# AVR_Board_4_0_Ports_-Old.net
KiCad netlist of a schematic drawn in Altium Designer
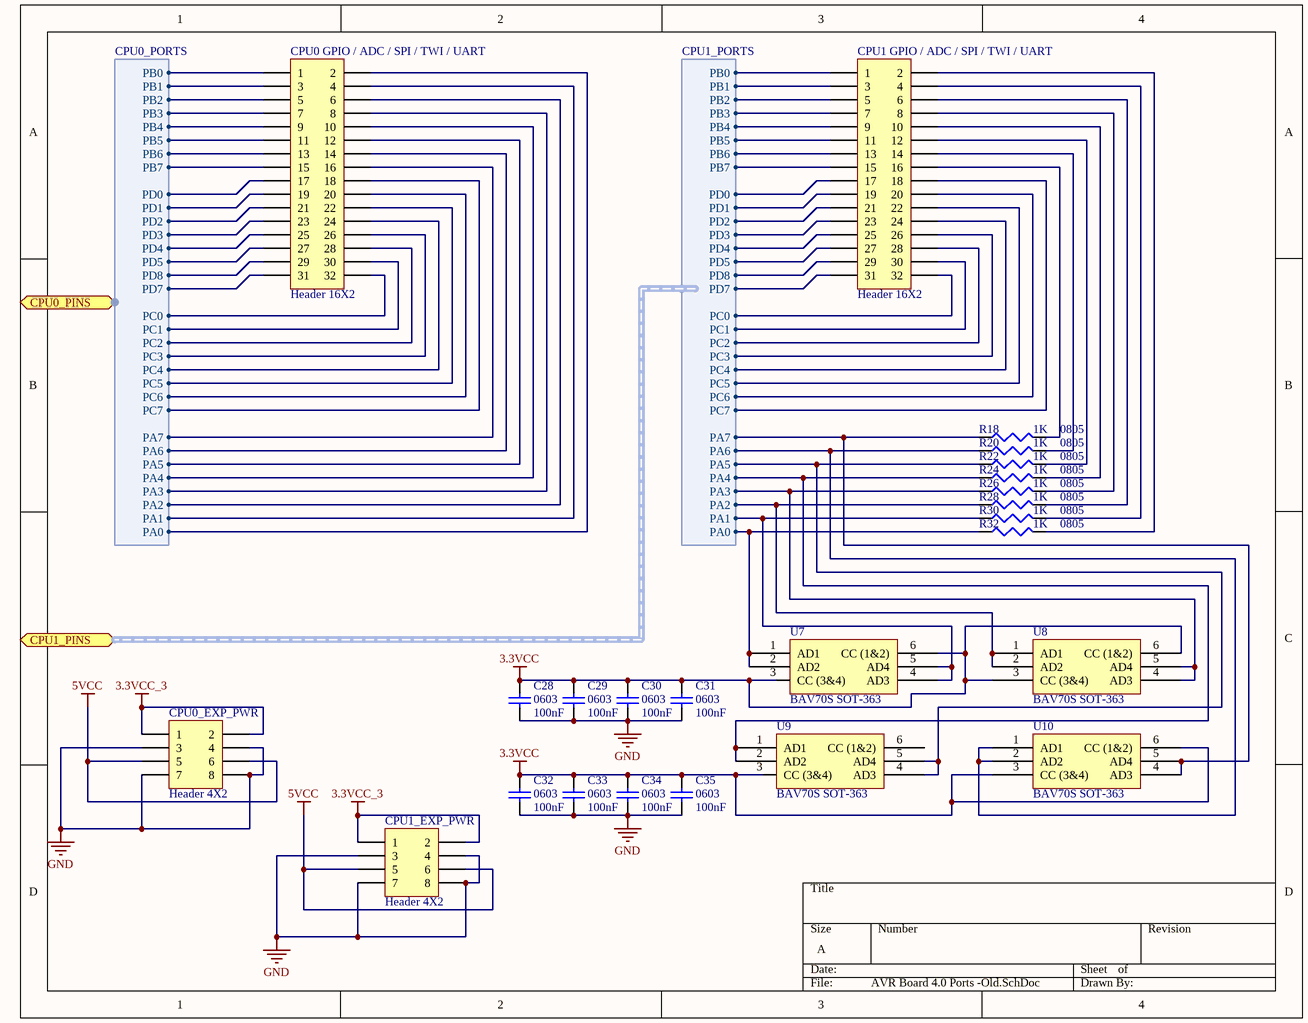
[diagram p0: AVR Board 4.0 Ports -Old.SchDoc]

(export (version "E")
  (design (tool "Eeschema 10.0.6"))
  (components
    (comp (ref "C28")
      (value "0603")
      (footprint "C1206")
      (description "Capacitor (Semiconductor SIM Model)")
      (fields (field (name "ALTIUM_VALUE") "100nF") (field (name "PUBLISHER") "Altium Limited"))
      (libsource (lib "Miscellaneous Devices") (part "Cap Semi"))
    )
    (comp (ref "C29")
      (value "0603")
      (footprint "C1206")
      (description "Capacitor (Semiconductor SIM Model)")
      (fields (field (name "ALTIUM_VALUE") "100nF") (field (name "PUBLISHER") "Altium Limited"))
      (libsource (lib "Miscellaneous Devices") (part "Cap Semi"))
    )
    (comp (ref "C30")
      (value "0603")
      (footprint "C1206")
      (description "Capacitor (Semiconductor SIM Model)")
      (fields (field (name "ALTIUM_VALUE") "100nF") (field (name "PUBLISHER") "Altium Limited"))
      (libsource (lib "Miscellaneous Devices") (part "Cap Semi"))
    )
    (comp (ref "C31")
      (value "0603")
      (footprint "C1206")
      (description "Capacitor (Semiconductor SIM Model)")
      (fields (field (name "ALTIUM_VALUE") "100nF") (field (name "PUBLISHER") "Altium Limited"))
      (libsource (lib "Miscellaneous Devices") (part "Cap Semi"))
    )
    (comp (ref "C32")
      (value "0603")
      (footprint "C1206")
      (description "Capacitor (Semiconductor SIM Model)")
      (fields (field (name "ALTIUM_VALUE") "100nF") (field (name "PUBLISHER") "Altium Limited"))
      (libsource (lib "Miscellaneous Devices") (part "Cap Semi"))
    )
    (comp (ref "C33")
      (value "0603")
      (footprint "C1206")
      (description "Capacitor (Semiconductor SIM Model)")
      (fields (field (name "ALTIUM_VALUE") "100nF") (field (name "PUBLISHER") "Altium Limited"))
      (libsource (lib "Miscellaneous Devices") (part "Cap Semi"))
    )
    (comp (ref "C34")
      (value "0603")
      (footprint "C1206")
      (description "Capacitor (Semiconductor SIM Model)")
      (fields (field (name "ALTIUM_VALUE") "100nF") (field (name "PUBLISHER") "Altium Limited"))
      (libsource (lib "Miscellaneous Devices") (part "Cap Semi"))
    )
    (comp (ref "C35")
      (value "0603")
      (footprint "C1206")
      (description "Capacitor (Semiconductor SIM Model)")
      (fields (field (name "ALTIUM_VALUE") "100nF") (field (name "PUBLISHER") "Altium Limited"))
      (libsource (lib "Miscellaneous Devices") (part "Cap Semi"))
    )
    (comp (ref "CPU0 GPIO / ADC / SPI / TWI / UART")
      (value "Header 16X2")
      (footprint "HDR2X16")
      (description "Header, 16-Pin, Dual row")
      (fields (field (name "PUBLISHER") "Altium Limited"))
      (libsource (lib "Miscellaneous Connectors") (part "Header 16X2"))
    )
    (comp (ref "CPU0_EXP_PWR")
      (value "Header 4X2")
      (footprint "HDR2X4")
      (description "Header, 4-Pin, Dual row")
      (fields (field (name "PUBLISHER") "Altium Limited"))
      (libsource (lib "Miscellaneous Connectors") (part "Header 4X2"))
    )
    (comp (ref "CPU1 GPIO / ADC / SPI / TWI / UART")
      (value "Header 16X2")
      (footprint "HDR2X16")
      (description "Header, 16-Pin, Dual row")
      (fields (field (name "PUBLISHER") "Altium Limited"))
      (libsource (lib "Miscellaneous Connectors") (part "Header 16X2"))
    )
    (comp (ref "CPU1_EXP_PWR")
      (value "Header 4X2")
      (footprint "HDR2X4")
      (description "Header, 4-Pin, Dual row")
      (fields (field (name "PUBLISHER") "Altium Limited"))
      (libsource (lib "Miscellaneous Connectors") (part "Header 4X2"))
    )
    (comp (ref "R18")
      (value "0805")
      (footprint "SM 0805 - gap trimmed")
      (description "Resistor")
      (fields (field (name "ALTIUM_VALUE") "1K") (field (name "PUBLISHER") "Altium Limited"))
      (libsource (lib "Miscellaneous Devices") (part "Res3"))
    )
    (comp (ref "R20")
      (value "0805")
      (footprint "SM 0805 - gap trimmed")
      (description "Resistor")
      (fields (field (name "ALTIUM_VALUE") "1K") (field (name "PUBLISHER") "Altium Limited"))
      (libsource (lib "Miscellaneous Devices") (part "Res3"))
    )
    (comp (ref "R22")
      (value "0805")
      (footprint "SM 0805 - gap trimmed")
      (description "Resistor")
      (fields (field (name "ALTIUM_VALUE") "1K") (field (name "PUBLISHER") "Altium Limited"))
      (libsource (lib "Miscellaneous Devices") (part "Res3"))
    )
    (comp (ref "R24")
      (value "0805")
      (footprint "SM 0805 - gap trimmed")
      (description "Resistor")
      (fields (field (name "ALTIUM_VALUE") "1K") (field (name "PUBLISHER") "Altium Limited"))
      (libsource (lib "Miscellaneous Devices") (part "Res3"))
    )
    (comp (ref "R26")
      (value "0805")
      (footprint "SM 0805 - gap trimmed")
      (description "Resistor")
      (fields (field (name "ALTIUM_VALUE") "1K") (field (name "PUBLISHER") "Altium Limited"))
      (libsource (lib "Miscellaneous Devices") (part "Res3"))
    )
    (comp (ref "R28")
      (value "0805")
      (footprint "SM 0805 - gap trimmed")
      (description "Resistor")
      (fields (field (name "ALTIUM_VALUE") "1K") (field (name "PUBLISHER") "Altium Limited"))
      (libsource (lib "Miscellaneous Devices") (part "Res3"))
    )
    (comp (ref "R30")
      (value "0805")
      (footprint "SM 0805 - gap trimmed")
      (description "Resistor")
      (fields (field (name "ALTIUM_VALUE") "1K") (field (name "PUBLISHER") "Altium Limited"))
      (libsource (lib "Miscellaneous Devices") (part "Res3"))
    )
    (comp (ref "R32")
      (value "0805")
      (footprint "SM 0805 - gap trimmed")
      (description "Resistor")
      (fields (field (name "ALTIUM_VALUE") "1K") (field (name "PUBLISHER") "Altium Limited"))
      (libsource (lib "Miscellaneous Devices") (part "Res3"))
    )
    (comp (ref "U7")
      (value "BAV70S SOT-363")
      (footprint "BAV70S_SOT363")
      (libsource (lib "Adams Altium Library") (part "BAV70S SOT-363"))
    )
    (comp (ref "U8")
      (value "BAV70S SOT-363")
      (footprint "BAV70S_SOT363")
      (libsource (lib "Adams Altium Library") (part "BAV70S SOT-363"))
    )
    (comp (ref "U9")
      (value "BAV70S SOT-363")
      (footprint "BAV70S_SOT363")
      (libsource (lib "Adams Altium Library") (part "BAV70S SOT-363"))
    )
    (comp (ref "U10")
      (value "BAV70S SOT-363")
      (footprint "BAV70S_SOT363")
      (libsource (lib "Adams Altium Library") (part "BAV70S SOT-363"))
    )
  )
  (nets
    (net (code "5") (name "3.3VCC") (class "Default")
      (node (ref "C28") (pin "2") (pinfunction "2_2") (pintype "passive"))
      (node (ref "C29") (pin "2") (pinfunction "2_2") (pintype "passive"))
      (node (ref "C30") (pin "2") (pinfunction "2_2") (pintype "passive"))
      (node (ref "C31") (pin "2") (pinfunction "2_2") (pintype "passive"))
      (node (ref "C32") (pin "2") (pinfunction "2_2") (pintype "passive"))
      (node (ref "C33") (pin "2") (pinfunction "2_2") (pintype "passive"))
      (node (ref "C34") (pin "2") (pinfunction "2_2") (pintype "passive"))
      (node (ref "C35") (pin "2") (pinfunction "2_2") (pintype "passive"))
      (node (ref "U10") (pin "3") (pinfunction "CC_(3&4)_3") (pintype "passive"))
      (node (ref "U10") (pin "6") (pinfunction "CC_(1&2)_6") (pintype "passive"))
      (node (ref "U7") (pin "3") (pinfunction "CC_(3&4)_3") (pintype "passive"))
      (node (ref "U7") (pin "6") (pinfunction "CC_(1&2)_6") (pintype "passive"))
      (node (ref "U8") (pin "3") (pinfunction "CC_(3&4)_3") (pintype "passive"))
      (node (ref "U8") (pin "6") (pinfunction "CC_(1&2)_6") (pintype "passive"))
      (node (ref "U9") (pin "3") (pinfunction "CC_(3&4)_3") (pintype "passive"))
    )
    (net (code "6") (name "3.3VCC_3") (class "Default")
      (node (ref "CPU0_EXP_PWR") (pin "1") (pinfunction "1_1") (pintype "passive"))
      (node (ref "CPU0_EXP_PWR") (pin "2") (pinfunction "2_2") (pintype "passive"))
      (node (ref "CPU1_EXP_PWR") (pin "1") (pinfunction "1_1") (pintype "passive"))
      (node (ref "CPU1_EXP_PWR") (pin "2") (pinfunction "2_2") (pintype "passive"))
    )
    (net (code "7") (name "5VCC") (class "Default")
      (node (ref "CPU0_EXP_PWR") (pin "5") (pinfunction "5_5") (pintype "passive"))
      (node (ref "CPU0_EXP_PWR") (pin "6") (pinfunction "6_6") (pintype "passive"))
      (node (ref "CPU1_EXP_PWR") (pin "5") (pinfunction "5_5") (pintype "passive"))
      (node (ref "CPU1_EXP_PWR") (pin "6") (pinfunction "6_6") (pintype "passive"))
    )
    (net (code "8") (name "GND") (class "Default")
      (node (ref "C28") (pin "1") (pinfunction "1_1") (pintype "passive"))
      (node (ref "C29") (pin "1") (pinfunction "1_1") (pintype "passive"))
      (node (ref "C30") (pin "1") (pinfunction "1_1") (pintype "passive"))
      (node (ref "C31") (pin "1") (pinfunction "1_1") (pintype "passive"))
      (node (ref "C32") (pin "1") (pinfunction "1_1") (pintype "passive"))
      (node (ref "C33") (pin "1") (pinfunction "1_1") (pintype "passive"))
      (node (ref "C34") (pin "1") (pinfunction "1_1") (pintype "passive"))
      (node (ref "C35") (pin "1") (pinfunction "1_1") (pintype "passive"))
      (node (ref "CPU0_EXP_PWR") (pin "3") (pinfunction "3_3") (pintype "passive"))
      (node (ref "CPU0_EXP_PWR") (pin "4") (pinfunction "4_4") (pintype "passive"))
      (node (ref "CPU0_EXP_PWR") (pin "7") (pinfunction "7_7") (pintype "passive"))
      (node (ref "CPU0_EXP_PWR") (pin "8") (pinfunction "8_8") (pintype "passive"))
      (node (ref "CPU1_EXP_PWR") (pin "3") (pinfunction "3_3") (pintype "passive"))
      (node (ref "CPU1_EXP_PWR") (pin "4") (pinfunction "4_4") (pintype "passive"))
      (node (ref "CPU1_EXP_PWR") (pin "7") (pinfunction "7_7") (pintype "passive"))
      (node (ref "CPU1_EXP_PWR") (pin "8") (pinfunction "8_8") (pintype "passive"))
    )
    (net (code "9") (name "Net-(CPU1 GPIO / ADC / SPI / TWI / UART-Pad2)") (class "Default")
      (node (ref "CPU1 GPIO / ADC / SPI / TWI / UART") (pin "2") (pinfunction "2_2") (pintype "passive"))
      (node (ref "R32") (pin "2") (pinfunction "2_2") (pintype "passive"))
    )
    (net (code "10") (name "Net-(CPU1 GPIO / ADC / SPI / TWI / UART-Pad4)") (class "Default")
      (node (ref "CPU1 GPIO / ADC / SPI / TWI / UART") (pin "4") (pinfunction "4_4") (pintype "passive"))
      (node (ref "R30") (pin "2") (pinfunction "2_2") (pintype "passive"))
    )
    (net (code "11") (name "Net-(CPU1 GPIO / ADC / SPI / TWI / UART-Pad6)") (class "Default")
      (node (ref "CPU1 GPIO / ADC / SPI / TWI / UART") (pin "6") (pinfunction "6_6") (pintype "passive"))
      (node (ref "R28") (pin "2") (pinfunction "2_2") (pintype "passive"))
    )
    (net (code "12") (name "Net-(CPU1 GPIO / ADC / SPI / TWI / UART-Pad8)") (class "Default")
      (node (ref "CPU1 GPIO / ADC / SPI / TWI / UART") (pin "8") (pinfunction "8_8") (pintype "passive"))
      (node (ref "R26") (pin "2") (pinfunction "2_2") (pintype "passive"))
    )
    (net (code "13") (name "Net-(CPU1 GPIO / ADC / SPI / TWI / UART-Pad10)") (class "Default")
      (node (ref "CPU1 GPIO / ADC / SPI / TWI / UART") (pin "10") (pinfunction "10_10") (pintype "passive"))
      (node (ref "R24") (pin "2") (pinfunction "2_2") (pintype "passive"))
    )
    (net (code "14") (name "Net-(CPU1 GPIO / ADC / SPI / TWI / UART-Pad12)") (class "Default")
      (node (ref "CPU1 GPIO / ADC / SPI / TWI / UART") (pin "12") (pinfunction "12_12") (pintype "passive"))
      (node (ref "R22") (pin "2") (pinfunction "2_2") (pintype "passive"))
    )
    (net (code "15") (name "Net-(CPU1 GPIO / ADC / SPI / TWI / UART-Pad14)") (class "Default")
      (node (ref "CPU1 GPIO / ADC / SPI / TWI / UART") (pin "14") (pinfunction "14_14") (pintype "passive"))
      (node (ref "R20") (pin "2") (pinfunction "2_2") (pintype "passive"))
    )
    (net (code "16") (name "Net-(CPU1 GPIO / ADC / SPI / TWI / UART-Pad16)") (class "Default")
      (node (ref "CPU1 GPIO / ADC / SPI / TWI / UART") (pin "16") (pinfunction "16_16") (pintype "passive"))
      (node (ref "R18") (pin "2") (pinfunction "2_2") (pintype "passive"))
    )
    (net (code "17") (name "Net-(U7-AD1)") (class "Default")
      (node (ref "R32") (pin "1") (pinfunction "1_1") (pintype "passive"))
      (node (ref "U7") (pin "1") (pinfunction "AD1_1") (pintype "passive"))
      (node (ref "U7") (pin "2") (pinfunction "AD2_2") (pintype "passive"))
    )
    (net (code "18") (name "Net-(U7-AD3)") (class "Default")
      (node (ref "R30") (pin "1") (pinfunction "1_1") (pintype "passive"))
      (node (ref "U7") (pin "4") (pinfunction "AD3_4") (pintype "passive"))
      (node (ref "U7") (pin "5") (pinfunction "AD4_5") (pintype "passive"))
    )
    (net (code "19") (name "Net-(U8-AD1)") (class "Default")
      (node (ref "R28") (pin "1") (pinfunction "1_1") (pintype "passive"))
      (node (ref "U8") (pin "1") (pinfunction "AD1_1") (pintype "passive"))
      (node (ref "U8") (pin "2") (pinfunction "AD2_2") (pintype "passive"))
    )
    (net (code "20") (name "Net-(U8-AD3)") (class "Default")
      (node (ref "R26") (pin "1") (pinfunction "1_1") (pintype "passive"))
      (node (ref "U8") (pin "4") (pinfunction "AD3_4") (pintype "passive"))
      (node (ref "U8") (pin "5") (pinfunction "AD4_5") (pintype "passive"))
    )
    (net (code "21") (name "Net-(U9-AD1)") (class "Default")
      (node (ref "R24") (pin "1") (pinfunction "1_1") (pintype "passive"))
      (node (ref "U9") (pin "1") (pinfunction "AD1_1") (pintype "passive"))
      (node (ref "U9") (pin "2") (pinfunction "AD2_2") (pintype "passive"))
    )
    (net (code "22") (name "Net-(U9-AD3)") (class "Default")
      (node (ref "R22") (pin "1") (pinfunction "1_1") (pintype "passive"))
      (node (ref "U9") (pin "4") (pinfunction "AD3_4") (pintype "passive"))
      (node (ref "U9") (pin "5") (pinfunction "AD4_5") (pintype "passive"))
    )
    (net (code "23") (name "Net-(U10-AD1)") (class "Default")
      (node (ref "R20") (pin "1") (pinfunction "1_1") (pintype "passive"))
      (node (ref "U10") (pin "1") (pinfunction "AD1_1") (pintype "passive"))
      (node (ref "U10") (pin "2") (pinfunction "AD2_2") (pintype "passive"))
    )
    (net (code "24") (name "Net-(U10-AD3)") (class "Default")
      (node (ref "R18") (pin "1") (pinfunction "1_1") (pintype "passive"))
      (node (ref "U10") (pin "4") (pinfunction "AD3_4") (pintype "passive"))
      (node (ref "U10") (pin "5") (pinfunction "AD4_5") (pintype "passive"))
    )
    (net (code "25") (name "unconnected-(CPU0 GPIO / ADC / SPI / TWI / UART-Pad1)") (class "Default")
      (node (ref "CPU0 GPIO / ADC / SPI / TWI / UART") (pin "1") (pinfunction "1_1") (pintype "passive"))
    )
    (net (code "26") (name "unconnected-(CPU0 GPIO / ADC / SPI / TWI / UART-Pad2)") (class "Default")
      (node (ref "CPU0 GPIO / ADC / SPI / TWI / UART") (pin "2") (pinfunction "2_2") (pintype "passive"))
    )
    (net (code "27") (name "unconnected-(CPU0 GPIO / ADC / SPI / TWI / UART-Pad3)") (class "Default")
      (node (ref "CPU0 GPIO / ADC / SPI / TWI / UART") (pin "3") (pinfunction "3_3") (pintype "passive"))
    )
    (net (code "28") (name "unconnected-(CPU0 GPIO / ADC / SPI / TWI / UART-Pad4)") (class "Default")
      (node (ref "CPU0 GPIO / ADC / SPI / TWI / UART") (pin "4") (pinfunction "4_4") (pintype "passive"))
    )
    (net (code "29") (name "unconnected-(CPU0 GPIO / ADC / SPI / TWI / UART-Pad5)") (class "Default")
      (node (ref "CPU0 GPIO / ADC / SPI / TWI / UART") (pin "5") (pinfunction "5_5") (pintype "passive"))
    )
    (net (code "30") (name "unconnected-(CPU0 GPIO / ADC / SPI / TWI / UART-Pad6)") (class "Default")
      (node (ref "CPU0 GPIO / ADC / SPI / TWI / UART") (pin "6") (pinfunction "6_6") (pintype "passive"))
    )
    (net (code "31") (name "unconnected-(CPU0 GPIO / ADC / SPI / TWI / UART-Pad7)") (class "Default")
      (node (ref "CPU0 GPIO / ADC / SPI / TWI / UART") (pin "7") (pinfunction "7_7") (pintype "passive"))
    )
    (net (code "32") (name "unconnected-(CPU0 GPIO / ADC / SPI / TWI / UART-Pad8)") (class "Default")
      (node (ref "CPU0 GPIO / ADC / SPI / TWI / UART") (pin "8") (pinfunction "8_8") (pintype "passive"))
    )
    (net (code "33") (name "unconnected-(CPU0 GPIO / ADC / SPI / TWI / UART-Pad9)") (class "Default")
      (node (ref "CPU0 GPIO / ADC / SPI / TWI / UART") (pin "9") (pinfunction "9_9") (pintype "passive"))
    )
    (net (code "34") (name "unconnected-(CPU0 GPIO / ADC / SPI / TWI / UART-Pad10)") (class "Default")
      (node (ref "CPU0 GPIO / ADC / SPI / TWI / UART") (pin "10") (pinfunction "10_10") (pintype "passive"))
    )
    (net (code "35") (name "unconnected-(CPU0 GPIO / ADC / SPI / TWI / UART-Pad11)") (class "Default")
      (node (ref "CPU0 GPIO / ADC / SPI / TWI / UART") (pin "11") (pinfunction "11_11") (pintype "passive"))
    )
    (net (code "36") (name "unconnected-(CPU0 GPIO / ADC / SPI / TWI / UART-Pad12)") (class "Default")
      (node (ref "CPU0 GPIO / ADC / SPI / TWI / UART") (pin "12") (pinfunction "12_12") (pintype "passive"))
    )
    (net (code "37") (name "unconnected-(CPU0 GPIO / ADC / SPI / TWI / UART-Pad13)") (class "Default")
      (node (ref "CPU0 GPIO / ADC / SPI / TWI / UART") (pin "13") (pinfunction "13_13") (pintype "passive"))
    )
    (net (code "38") (name "unconnected-(CPU0 GPIO / ADC / SPI / TWI / UART-Pad14)") (class "Default")
      (node (ref "CPU0 GPIO / ADC / SPI / TWI / UART") (pin "14") (pinfunction "14_14") (pintype "passive"))
    )
    (net (code "39") (name "unconnected-(CPU0 GPIO / ADC / SPI / TWI / UART-Pad15)") (class "Default")
      (node (ref "CPU0 GPIO / ADC / SPI / TWI / UART") (pin "15") (pinfunction "15_15") (pintype "passive"))
    )
    (net (code "40") (name "unconnected-(CPU0 GPIO / ADC / SPI / TWI / UART-Pad16)") (class "Default")
      (node (ref "CPU0 GPIO / ADC / SPI / TWI / UART") (pin "16") (pinfunction "16_16") (pintype "passive"))
    )
    (net (code "41") (name "unconnected-(CPU0 GPIO / ADC / SPI / TWI / UART-Pad17)") (class "Default")
      (node (ref "CPU0 GPIO / ADC / SPI / TWI / UART") (pin "17") (pinfunction "17_17") (pintype "passive"))
    )
    (net (code "42") (name "unconnected-(CPU0 GPIO / ADC / SPI / TWI / UART-Pad18)") (class "Default")
      (node (ref "CPU0 GPIO / ADC / SPI / TWI / UART") (pin "18") (pinfunction "18_18") (pintype "passive"))
    )
    (net (code "43") (name "unconnected-(CPU0 GPIO / ADC / SPI / TWI / UART-Pad19)") (class "Default")
      (node (ref "CPU0 GPIO / ADC / SPI / TWI / UART") (pin "19") (pinfunction "19_19") (pintype "passive"))
    )
    (net (code "44") (name "unconnected-(CPU0 GPIO / ADC / SPI / TWI / UART-Pad20)") (class "Default")
      (node (ref "CPU0 GPIO / ADC / SPI / TWI / UART") (pin "20") (pinfunction "20_20") (pintype "passive"))
    )
    (net (code "45") (name "unconnected-(CPU0 GPIO / ADC / SPI / TWI / UART-Pad21)") (class "Default")
      (node (ref "CPU0 GPIO / ADC / SPI / TWI / UART") (pin "21") (pinfunction "21_21") (pintype "passive"))
    )
    (net (code "46") (name "unconnected-(CPU0 GPIO / ADC / SPI / TWI / UART-Pad22)") (class "Default")
      (node (ref "CPU0 GPIO / ADC / SPI / TWI / UART") (pin "22") (pinfunction "22_22") (pintype "passive"))
    )
    (net (code "47") (name "unconnected-(CPU0 GPIO / ADC / SPI / TWI / UART-Pad23)") (class "Default")
      (node (ref "CPU0 GPIO / ADC / SPI / TWI / UART") (pin "23") (pinfunction "23_23") (pintype "passive"))
    )
    (net (code "48") (name "unconnected-(CPU0 GPIO / ADC / SPI / TWI / UART-Pad24)") (class "Default")
      (node (ref "CPU0 GPIO / ADC / SPI / TWI / UART") (pin "24") (pinfunction "24_24") (pintype "passive"))
    )
    (net (code "49") (name "unconnected-(CPU0 GPIO / ADC / SPI / TWI / UART-Pad25)") (class "Default")
      (node (ref "CPU0 GPIO / ADC / SPI / TWI / UART") (pin "25") (pinfunction "25_25") (pintype "passive"))
    )
    (net (code "50") (name "unconnected-(CPU0 GPIO / ADC / SPI / TWI / UART-Pad26)") (class "Default")
      (node (ref "CPU0 GPIO / ADC / SPI / TWI / UART") (pin "26") (pinfunction "26_26") (pintype "passive"))
    )
    (net (code "51") (name "unconnected-(CPU0 GPIO / ADC / SPI / TWI / UART-Pad27)") (class "Default")
      (node (ref "CPU0 GPIO / ADC / SPI / TWI / UART") (pin "27") (pinfunction "27_27") (pintype "passive"))
    )
    (net (code "52") (name "unconnected-(CPU0 GPIO / ADC / SPI / TWI / UART-Pad28)") (class "Default")
      (node (ref "CPU0 GPIO / ADC / SPI / TWI / UART") (pin "28") (pinfunction "28_28") (pintype "passive"))
    )
    (net (code "53") (name "unconnected-(CPU0 GPIO / ADC / SPI / TWI / UART-Pad29)") (class "Default")
      (node (ref "CPU0 GPIO / ADC / SPI / TWI / UART") (pin "29") (pinfunction "29_29") (pintype "passive"))
    )
    (net (code "54") (name "unconnected-(CPU0 GPIO / ADC / SPI / TWI / UART-Pad30)") (class "Default")
      (node (ref "CPU0 GPIO / ADC / SPI / TWI / UART") (pin "30") (pinfunction "30_30") (pintype "passive"))
    )
    (net (code "55") (name "unconnected-(CPU0 GPIO / ADC / SPI / TWI / UART-Pad31)") (class "Default")
      (node (ref "CPU0 GPIO / ADC / SPI / TWI / UART") (pin "31") (pinfunction "31_31") (pintype "passive"))
    )
    (net (code "56") (name "unconnected-(CPU0 GPIO / ADC / SPI / TWI / UART-Pad32)") (class "Default")
      (node (ref "CPU0 GPIO / ADC / SPI / TWI / UART") (pin "32") (pinfunction "32_32") (pintype "passive"))
    )
    (net (code "57") (name "unconnected-(CPU1 GPIO / ADC / SPI / TWI / UART-Pad1)") (class "Default")
      (node (ref "CPU1 GPIO / ADC / SPI / TWI / UART") (pin "1") (pinfunction "1_1") (pintype "passive"))
    )
    (net (code "58") (name "unconnected-(CPU1 GPIO / ADC / SPI / TWI / UART-Pad3)") (class "Default")
      (node (ref "CPU1 GPIO / ADC / SPI / TWI / UART") (pin "3") (pinfunction "3_3") (pintype "passive"))
    )
    (net (code "59") (name "unconnected-(CPU1 GPIO / ADC / SPI / TWI / UART-Pad5)") (class "Default")
      (node (ref "CPU1 GPIO / ADC / SPI / TWI / UART") (pin "5") (pinfunction "5_5") (pintype "passive"))
    )
    (net (code "60") (name "unconnected-(CPU1 GPIO / ADC / SPI / TWI / UART-Pad7)") (class "Default")
      (node (ref "CPU1 GPIO / ADC / SPI / TWI / UART") (pin "7") (pinfunction "7_7") (pintype "passive"))
    )
    (net (code "61") (name "unconnected-(CPU1 GPIO / ADC / SPI / TWI / UART-Pad9)") (class "Default")
      (node (ref "CPU1 GPIO / ADC / SPI / TWI / UART") (pin "9") (pinfunction "9_9") (pintype "passive"))
    )
    (net (code "62") (name "unconnected-(CPU1 GPIO / ADC / SPI / TWI / UART-Pad11)") (class "Default")
      (node (ref "CPU1 GPIO / ADC / SPI / TWI / UART") (pin "11") (pinfunction "11_11") (pintype "passive"))
    )
    (net (code "63") (name "unconnected-(CPU1 GPIO / ADC / SPI / TWI / UART-Pad13)") (class "Default")
      (node (ref "CPU1 GPIO / ADC / SPI / TWI / UART") (pin "13") (pinfunction "13_13") (pintype "passive"))
    )
    (net (code "64") (name "unconnected-(CPU1 GPIO / ADC / SPI / TWI / UART-Pad15)") (class "Default")
      (node (ref "CPU1 GPIO / ADC / SPI / TWI / UART") (pin "15") (pinfunction "15_15") (pintype "passive"))
    )
    (net (code "65") (name "unconnected-(CPU1 GPIO / ADC / SPI / TWI / UART-Pad17)") (class "Default")
      (node (ref "CPU1 GPIO / ADC / SPI / TWI / UART") (pin "17") (pinfunction "17_17") (pintype "passive"))
    )
    (net (code "66") (name "unconnected-(CPU1 GPIO / ADC / SPI / TWI / UART-Pad18)") (class "Default")
      (node (ref "CPU1 GPIO / ADC / SPI / TWI / UART") (pin "18") (pinfunction "18_18") (pintype "passive"))
    )
    (net (code "67") (name "unconnected-(CPU1 GPIO / ADC / SPI / TWI / UART-Pad19)") (class "Default")
      (node (ref "CPU1 GPIO / ADC / SPI / TWI / UART") (pin "19") (pinfunction "19_19") (pintype "passive"))
    )
    (net (code "68") (name "unconnected-(CPU1 GPIO / ADC / SPI / TWI / UART-Pad20)") (class "Default")
      (node (ref "CPU1 GPIO / ADC / SPI / TWI / UART") (pin "20") (pinfunction "20_20") (pintype "passive"))
    )
    (net (code "69") (name "unconnected-(CPU1 GPIO / ADC / SPI / TWI / UART-Pad21)") (class "Default")
      (node (ref "CPU1 GPIO / ADC / SPI / TWI / UART") (pin "21") (pinfunction "21_21") (pintype "passive"))
    )
    (net (code "70") (name "unconnected-(CPU1 GPIO / ADC / SPI / TWI / UART-Pad22)") (class "Default")
      (node (ref "CPU1 GPIO / ADC / SPI / TWI / UART") (pin "22") (pinfunction "22_22") (pintype "passive"))
    )
    (net (code "71") (name "unconnected-(CPU1 GPIO / ADC / SPI / TWI / UART-Pad23)") (class "Default")
      (node (ref "CPU1 GPIO / ADC / SPI / TWI / UART") (pin "23") (pinfunction "23_23") (pintype "passive"))
    )
    (net (code "72") (name "unconnected-(CPU1 GPIO / ADC / SPI / TWI / UART-Pad24)") (class "Default")
      (node (ref "CPU1 GPIO / ADC / SPI / TWI / UART") (pin "24") (pinfunction "24_24") (pintype "passive"))
    )
    (net (code "73") (name "unconnected-(CPU1 GPIO / ADC / SPI / TWI / UART-Pad25)") (class "Default")
      (node (ref "CPU1 GPIO / ADC / SPI / TWI / UART") (pin "25") (pinfunction "25_25") (pintype "passive"))
    )
    (net (code "74") (name "unconnected-(CPU1 GPIO / ADC / SPI / TWI / UART-Pad26)") (class "Default")
      (node (ref "CPU1 GPIO / ADC / SPI / TWI / UART") (pin "26") (pinfunction "26_26") (pintype "passive"))
    )
    (net (code "75") (name "unconnected-(CPU1 GPIO / ADC / SPI / TWI / UART-Pad27)") (class "Default")
      (node (ref "CPU1 GPIO / ADC / SPI / TWI / UART") (pin "27") (pinfunction "27_27") (pintype "passive"))
    )
    (net (code "76") (name "unconnected-(CPU1 GPIO / ADC / SPI / TWI / UART-Pad28)") (class "Default")
      (node (ref "CPU1 GPIO / ADC / SPI / TWI / UART") (pin "28") (pinfunction "28_28") (pintype "passive"))
    )
    (net (code "77") (name "unconnected-(CPU1 GPIO / ADC / SPI / TWI / UART-Pad29)") (class "Default")
      (node (ref "CPU1 GPIO / ADC / SPI / TWI / UART") (pin "29") (pinfunction "29_29") (pintype "passive"))
    )
    (net (code "78") (name "unconnected-(CPU1 GPIO / ADC / SPI / TWI / UART-Pad30)") (class "Default")
      (node (ref "CPU1 GPIO / ADC / SPI / TWI / UART") (pin "30") (pinfunction "30_30") (pintype "passive"))
    )
    (net (code "79") (name "unconnected-(CPU1 GPIO / ADC / SPI / TWI / UART-Pad31)") (class "Default")
      (node (ref "CPU1 GPIO / ADC / SPI / TWI / UART") (pin "31") (pinfunction "31_31") (pintype "passive"))
    )
    (net (code "80") (name "unconnected-(CPU1 GPIO / ADC / SPI / TWI / UART-Pad32)") (class "Default")
      (node (ref "CPU1 GPIO / ADC / SPI / TWI / UART") (pin "32") (pinfunction "32_32") (pintype "passive"))
    )
    (net (code "81") (name "unconnected-(U9-CC_(1&2)-Pad6)") (class "Default")
      (node (ref "U9") (pin "6") (pinfunction "CC_(1&2)_6") (pintype "passive"))
    )
  )
)
